# 2022_EDA_2.net
KiCad netlist of a schematic drawn in EasyEDA Pro
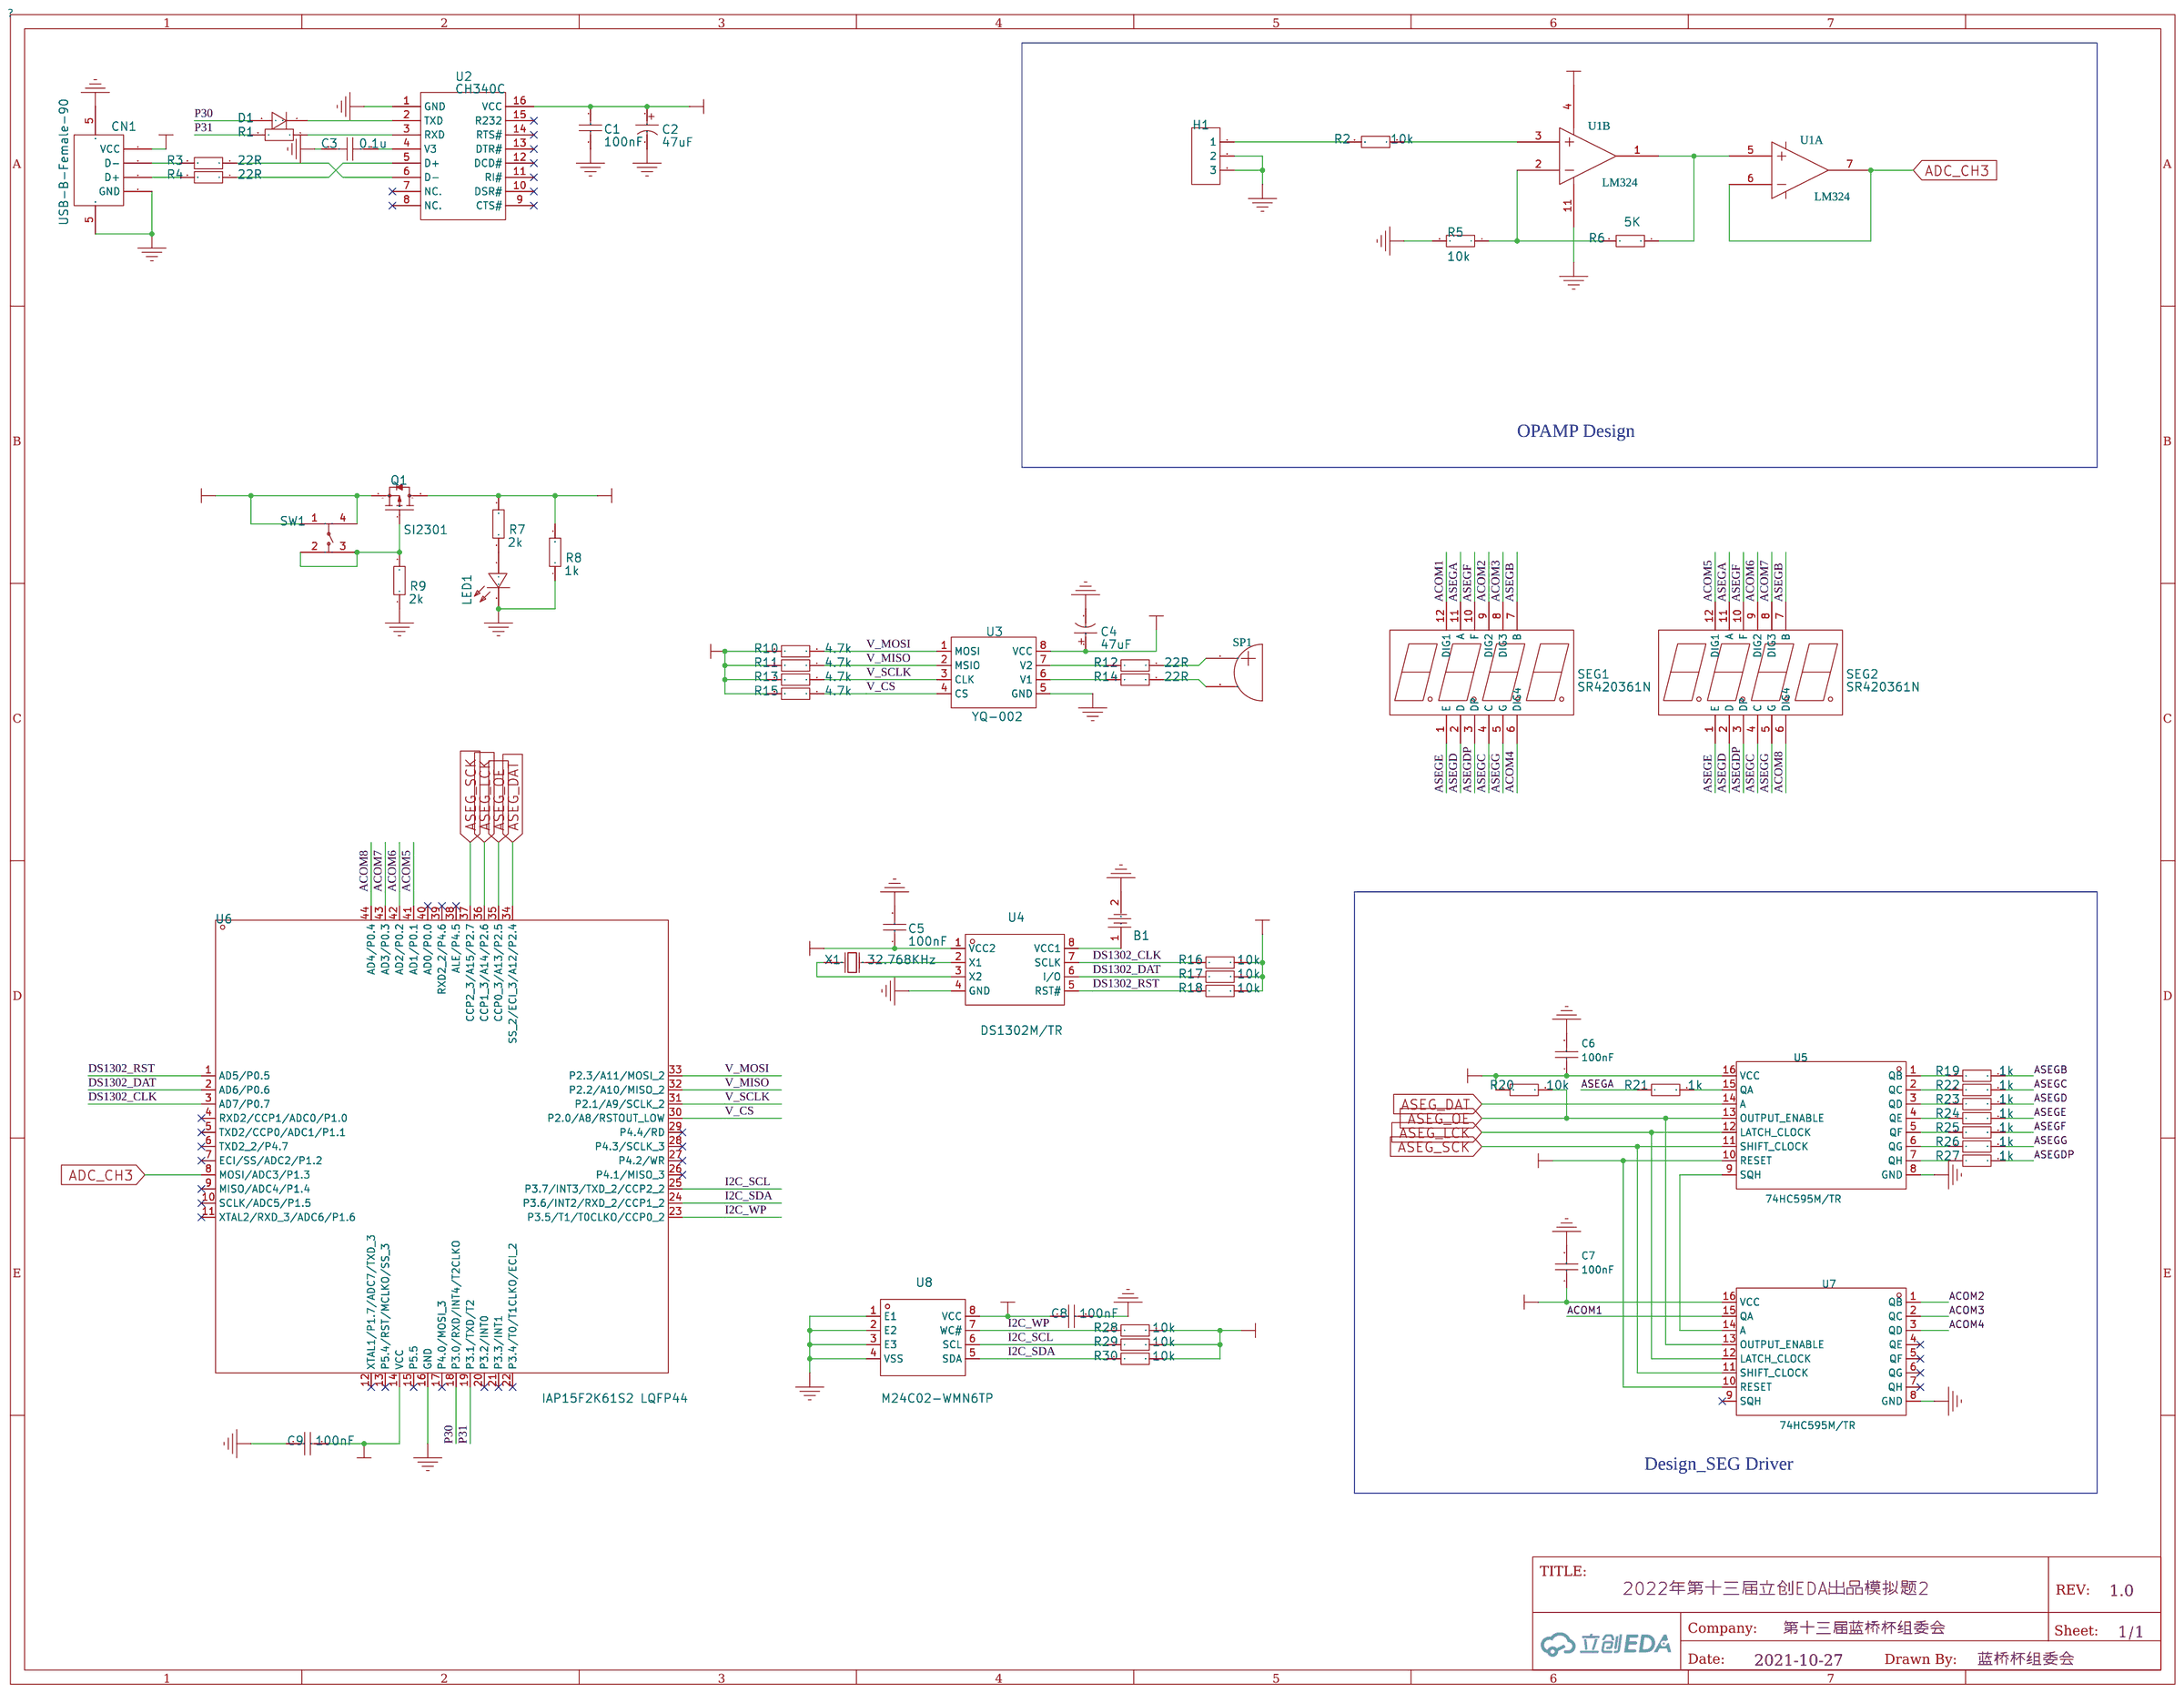
[diagram p0: schematic sheet]

(export (version "E")
  (design (tool "Eeschema 10.0.6"))
  (components
    (comp (ref "B1")
      (value "CR1220-2")
      (fields (field (name "Manufacturer") "Q&amp;J"))
      (libsource (lib "easyedapro") (part "CR1220-2"))
    )
    (comp (ref "C1")
      (value "100nF")
      (fields (field (name "Manufacturer Part") "0805F104M500NT") (field (name "Manufacturer") "FH"))
      (libsource (lib "easyedapro") (part "100nF"))
    )
    (comp (ref "C2")
      (value "47uF")
      (fields (field (name "Manufacturer Part") "VES470M1HTR-0607") (field (name "Manufacturer") "LELON"))
      (libsource (lib "easyedapro") (part "47uF"))
    )
    (comp (ref "C3") (value "0.1u") (libsource (lib "easyedapro") (part "0.1u")))
    (comp (ref "C4")
      (value "47uF")
      (fields (field (name "Manufacturer Part") "VES470M1HTR-0607") (field (name "Manufacturer") "LELON"))
      (libsource (lib "easyedapro") (part "47uF"))
    )
    (comp (ref "C5")
      (value "100nF")
      (fields (field (name "Manufacturer Part") "0805F104M500NT") (field (name "Manufacturer") "FH"))
      (libsource (lib "easyedapro") (part "100nF"))
    )
    (comp (ref "C6") (value "100nF") (libsource (lib "") (part "100nF_1")))
    (comp (ref "C7") (value "100nF") (libsource (lib "") (part "100nF_1")))
    (comp (ref "C8")
      (value "100nF")
      (fields (field (name "Manufacturer Part") "0805F104M500NT") (field (name "Manufacturer") "FH"))
      (libsource (lib "easyedapro") (part "100nF"))
    )
    (comp (ref "C9")
      (value "100nF")
      (fields (field (name "Manufacturer Part") "0805F104M500NT") (field (name "Manufacturer") "FH"))
      (libsource (lib "easyedapro") (part "100nF"))
    )
    (comp (ref "CN1")
      (value "USB-B-Female-90")
      (fields (field (name "Manufacturer Part") "USB-BF90") (field (name "Manufacturer") "ValuePro"))
      (libsource (lib "easyedapro") (part "USB-B-Female-90"))
    )
    (comp (ref "D1")
      (value "KLL4148")
      (fields (field (name "Manufacturer") "KEXIN"))
      (libsource (lib "easyedapro") (part "KLL4148"))
    )
    (comp (ref "H1") (value "HDR-F-2.54_1x3") (libsource (lib "easyedapro") (part "HDR-F-2.54_1x3")))
    (comp (ref "LED1")
      (value "17-21URC/TR8")
      (fields (field (name "Manufacturer") "Everlight Elec"))
      (libsource (lib "easyedapro") (part "17-21URC/TR8"))
    )
    (comp (ref "Q1")
      (value "SI2301")
      (fields (field (name "Manufacturer") "Hottech"))
      (libsource (lib "easyedapro") (part "SI2301"))
    )
    (comp (ref "R1")
      (value "1k")
      (fields (field (name "Manufacturer Part") "080500J0104T5E") (field (name "Manufacturer") "UniOhm"))
      (libsource (lib "easyedapro") (part "22R"))
    )
    (comp (ref "R2")
      (value "10k")
      (fields (field (name "Manufacturer Part") "080500J0104T5E") (field (name "Manufacturer") "UniOhm"))
      (libsource (lib "easyedapro") (part "22R"))
    )
    (comp (ref "R3")
      (value "22R")
      (fields (field (name "Manufacturer Part") "080500J0104T5E") (field (name "Manufacturer") "UniOhm"))
      (libsource (lib "easyedapro") (part "22R"))
    )
    (comp (ref "R4")
      (value "22R")
      (fields (field (name "Manufacturer Part") "080500J0104T5E") (field (name "Manufacturer") "UniOhm"))
      (libsource (lib "easyedapro") (part "22R"))
    )
    (comp (ref "R5")
      (value "10k")
      (fields (field (name "Manufacturer Part") "080500J0104T5E") (field (name "Manufacturer") "UniOhm"))
      (libsource (lib "easyedapro") (part "22R"))
    )
    (comp (ref "R6")
      (value "5K")
      (fields (field (name "Manufacturer Part") "080500J0104T5E") (field (name "Manufacturer") "UniOhm"))
      (libsource (lib "easyedapro") (part "22R"))
    )
    (comp (ref "R7")
      (value "2k")
      (fields (field (name "Manufacturer Part") "080500J0104T5E") (field (name "Manufacturer") "UniOhm"))
      (libsource (lib "easyedapro") (part "22R"))
    )
    (comp (ref "R8")
      (value "1k")
      (fields (field (name "Manufacturer Part") "080500J0104T5E") (field (name "Manufacturer") "UniOhm"))
      (libsource (lib "easyedapro") (part "22R"))
    )
    (comp (ref "R9")
      (value "2k")
      (fields (field (name "Manufacturer Part") "080500J0104T5E") (field (name "Manufacturer") "UniOhm"))
      (libsource (lib "easyedapro") (part "22R"))
    )
    (comp (ref "R10")
      (value "4.7k")
      (fields (field (name "Manufacturer Part") "080500J0104T5E") (field (name "Manufacturer") "UniOhm"))
      (libsource (lib "easyedapro") (part "22R"))
    )
    (comp (ref "R11")
      (value "4.7k")
      (fields (field (name "Manufacturer Part") "080500J0104T5E") (field (name "Manufacturer") "UniOhm"))
      (libsource (lib "easyedapro") (part "22R"))
    )
    (comp (ref "R12")
      (value "22R")
      (fields (field (name "Manufacturer Part") "080500J0104T5E") (field (name "Manufacturer") "UniOhm"))
      (libsource (lib "easyedapro") (part "22R"))
    )
    (comp (ref "R13")
      (value "4.7k")
      (fields (field (name "Manufacturer Part") "080500J0104T5E") (field (name "Manufacturer") "UniOhm"))
      (libsource (lib "easyedapro") (part "22R"))
    )
    (comp (ref "R14")
      (value "22R")
      (fields (field (name "Manufacturer Part") "080500J0104T5E") (field (name "Manufacturer") "UniOhm"))
      (libsource (lib "easyedapro") (part "22R"))
    )
    (comp (ref "R15")
      (value "4.7k")
      (fields (field (name "Manufacturer Part") "080500J0104T5E") (field (name "Manufacturer") "UniOhm"))
      (libsource (lib "easyedapro") (part "22R"))
    )
    (comp (ref "R16")
      (value "10k")
      (fields (field (name "Manufacturer Part") "080500J0104T5E") (field (name "Manufacturer") "UniOhm"))
      (libsource (lib "easyedapro") (part "22R"))
    )
    (comp (ref "R17")
      (value "10k")
      (fields (field (name "Manufacturer Part") "080500J0104T5E") (field (name "Manufacturer") "UniOhm"))
      (libsource (lib "easyedapro") (part "22R"))
    )
    (comp (ref "R18")
      (value "10k")
      (fields (field (name "Manufacturer Part") "080500J0104T5E") (field (name "Manufacturer") "UniOhm"))
      (libsource (lib "easyedapro") (part "22R"))
    )
    (comp (ref "R19")
      (value "1k")
      (fields (field (name "Manufacturer Part") "080500J0104T5E") (field (name "Manufacturer") "UniOhm"))
      (libsource (lib "easyedapro") (part "22R"))
    )
    (comp (ref "R20")
      (value "10k")
      (fields (field (name "Manufacturer Part") "080500J0104T5E") (field (name "Manufacturer") "UniOhm"))
      (libsource (lib "easyedapro") (part "22R"))
    )
    (comp (ref "R21")
      (value "1k")
      (fields (field (name "Manufacturer Part") "080500J0104T5E") (field (name "Manufacturer") "UniOhm"))
      (libsource (lib "easyedapro") (part "22R"))
    )
    (comp (ref "R22")
      (value "1k")
      (fields (field (name "Manufacturer Part") "080500J0104T5E") (field (name "Manufacturer") "UniOhm"))
      (libsource (lib "easyedapro") (part "22R"))
    )
    (comp (ref "R23")
      (value "1k")
      (fields (field (name "Manufacturer Part") "080500J0104T5E") (field (name "Manufacturer") "UniOhm"))
      (libsource (lib "easyedapro") (part "22R"))
    )
    (comp (ref "R24")
      (value "1k")
      (fields (field (name "Manufacturer Part") "080500J0104T5E") (field (name "Manufacturer") "UniOhm"))
      (libsource (lib "easyedapro") (part "22R"))
    )
    (comp (ref "R25")
      (value "1k")
      (fields (field (name "Manufacturer Part") "080500J0104T5E") (field (name "Manufacturer") "UniOhm"))
      (libsource (lib "easyedapro") (part "22R"))
    )
    (comp (ref "R26")
      (value "1k")
      (fields (field (name "Manufacturer Part") "080500J0104T5E") (field (name "Manufacturer") "UniOhm"))
      (libsource (lib "easyedapro") (part "22R"))
    )
    (comp (ref "R27")
      (value "1k")
      (fields (field (name "Manufacturer Part") "080500J0104T5E") (field (name "Manufacturer") "UniOhm"))
      (libsource (lib "easyedapro") (part "22R"))
    )
    (comp (ref "R28")
      (value "10k")
      (fields (field (name "Manufacturer Part") "080500J0104T5E") (field (name "Manufacturer") "UniOhm"))
      (libsource (lib "easyedapro") (part "22R"))
    )
    (comp (ref "R29")
      (value "10k")
      (fields (field (name "Manufacturer Part") "080500J0104T5E") (field (name "Manufacturer") "UniOhm"))
      (libsource (lib "easyedapro") (part "22R"))
    )
    (comp (ref "R30")
      (value "10k")
      (fields (field (name "Manufacturer Part") "080500J0104T5E") (field (name "Manufacturer") "UniOhm"))
      (libsource (lib "easyedapro") (part "22R"))
    )
    (comp (ref "SEG1")
      (value "SR420361N")
      (fields (field (name "Manufacturer") "Wuxi ARK Tech Elec"))
      (libsource (lib "easyedapro") (part "SR420361N"))
    )
    (comp (ref "SEG2")
      (value "SR420361N")
      (fields (field (name "Manufacturer") "Wuxi ARK Tech Elec"))
      (libsource (lib "easyedapro") (part "SR420361N"))
    )
    (comp (ref "SP1") (value "BUZZER") (libsource (lib "easyedapro") (part "BUZZER")))
    (comp (ref "SW1")
      (value "TS-1159UB-B-D-BL")
      (fields (field (name "Manufacturer") "XKB Connectivity"))
      (libsource (lib "easyedapro") (part "TS-1159UB-B-D-BL"))
    )
    (comp (ref "U1") (value "LM324") (libsource (lib "easyedapro") (part "LM324")))
    (comp (ref "U2")
      (value "CH340C")
      (fields (field (name "Manufacturer") "WCH"))
      (libsource (lib "easyedapro") (part "CH340C"))
    )
    (comp (ref "U3") (value "YQ-002") (libsource (lib "easyedapro") (part "YQ-002")))
    (comp (ref "U4")
      (value "DS1302M/TR")
      (fields (field (name "Manufacturer") "HGSEMI"))
      (libsource (lib "easyedapro") (part "DS1302M/TR"))
    )
    (comp (ref "U5") (value "74HC595M/TR") (libsource (lib "easyedapro") (part "74HC595M/TR")))
    (comp (ref "U6")
      (value "IAP15F2K61S2 LQFP44")
      (fields (field (name "Manufacturer") "STC"))
      (libsource (lib "easyedapro") (part "IAP15F2K61S2 LQFP44"))
    )
    (comp (ref "U7") (value "74HC595M/TR") (libsource (lib "easyedapro") (part "74HC595M/TR")))
    (comp (ref "U8")
      (value "M24C02-WMN6TP")
      (fields (field (name "Manufacturer") "STMicroelectronics"))
      (libsource (lib "easyedapro") (part "M24C02-WMN6TP"))
    )
    (comp (ref "X1")
      (value "32.768KHz")
      (fields
        (field (name "Manufacturer Part") "6K832768F12UB")
        (field (name "Manufacturer") "SHENZHEN CRYSTAL TECH")
      )
      (libsource (lib "easyedapro") (part "32.768KHz"))
    )
  )
  (nets
    (net (code "1") (name "/ACOM1") (class "Default")
      (node (ref "SEG1") (pin "12") (pinfunction "DIG1_12") (pintype "input"))
      (node (ref "U7") (pin "15") (pinfunction "QA_15") (pintype "input"))
    )
    (net (code "2") (name "/ACOM2") (class "Default")
      (node (ref "SEG1") (pin "9") (pinfunction "DIG2_9") (pintype "input"))
      (node (ref "U7") (pin "1") (pinfunction "QB_1") (pintype "input"))
    )
    (net (code "3") (name "/ACOM3") (class "Default")
      (node (ref "SEG1") (pin "8") (pinfunction "DIG3_8") (pintype "input"))
      (node (ref "U7") (pin "2") (pinfunction "QC_2") (pintype "input"))
    )
    (net (code "4") (name "/ACOM4") (class "Default")
      (node (ref "SEG1") (pin "6") (pinfunction "DIG4_6") (pintype "input"))
      (node (ref "U7") (pin "3") (pinfunction "QD_3") (pintype "input"))
    )
    (net (code "5") (name "/ACOM5") (class "Default")
      (node (ref "SEG2") (pin "12") (pinfunction "DIG1_12") (pintype "input"))
      (node (ref "U6") (pin "41") (pinfunction "AD1/P0.1_41") (pintype "input"))
    )
    (net (code "6") (name "/ACOM6") (class "Default")
      (node (ref "SEG2") (pin "9") (pinfunction "DIG2_9") (pintype "input"))
      (node (ref "U6") (pin "42") (pinfunction "AD2/P0.2_42") (pintype "input"))
    )
    (net (code "7") (name "/ACOM7") (class "Default")
      (node (ref "SEG2") (pin "8") (pinfunction "DIG3_8") (pintype "input"))
      (node (ref "U6") (pin "43") (pinfunction "AD3/P0.3_43") (pintype "input"))
    )
    (net (code "8") (name "/ACOM8") (class "Default")
      (node (ref "SEG2") (pin "6") (pinfunction "DIG4_6") (pintype "input"))
      (node (ref "U6") (pin "44") (pinfunction "AD4/P0.4_44") (pintype "input"))
    )
    (net (code "9") (name "/ASEGA") (class "Default")
      (node (ref "R21") (pin "1") (pinfunction "1_1") (pintype "input"))
      (node (ref "SEG1") (pin "11") (pinfunction "A_11") (pintype "input"))
      (node (ref "SEG2") (pin "11") (pinfunction "A_11") (pintype "input"))
    )
    (net (code "10") (name "/ASEGB") (class "Default")
      (node (ref "R19") (pin "2") (pinfunction "2_2") (pintype "input"))
      (node (ref "SEG1") (pin "7") (pinfunction "B_7") (pintype "input"))
      (node (ref "SEG2") (pin "7") (pinfunction "B_7") (pintype "input"))
    )
    (net (code "11") (name "/ASEGC") (class "Default")
      (node (ref "R22") (pin "2") (pinfunction "2_2") (pintype "input"))
      (node (ref "SEG1") (pin "4") (pinfunction "C_4") (pintype "input"))
      (node (ref "SEG2") (pin "4") (pinfunction "C_4") (pintype "input"))
    )
    (net (code "12") (name "/ASEGD") (class "Default")
      (node (ref "R23") (pin "2") (pinfunction "2_2") (pintype "input"))
      (node (ref "SEG1") (pin "2") (pinfunction "D_2") (pintype "input"))
      (node (ref "SEG2") (pin "2") (pinfunction "D_2") (pintype "input"))
    )
    (net (code "13") (name "/ASEGDP") (class "Default")
      (node (ref "R27") (pin "2") (pinfunction "2_2") (pintype "input"))
      (node (ref "SEG1") (pin "3") (pinfunction "DP_3") (pintype "input"))
      (node (ref "SEG2") (pin "3") (pinfunction "DP_3") (pintype "input"))
    )
    (net (code "14") (name "/ASEGE") (class "Default")
      (node (ref "R24") (pin "2") (pinfunction "2_2") (pintype "input"))
      (node (ref "SEG1") (pin "1") (pinfunction "E_1") (pintype "input"))
      (node (ref "SEG2") (pin "1") (pinfunction "E_1") (pintype "input"))
    )
    (net (code "15") (name "/ASEGF") (class "Default")
      (node (ref "R25") (pin "2") (pinfunction "2_2") (pintype "input"))
      (node (ref "SEG1") (pin "10") (pinfunction "F_10") (pintype "input"))
      (node (ref "SEG2") (pin "10") (pinfunction "F_10") (pintype "input"))
    )
    (net (code "16") (name "/ASEGG") (class "Default")
      (node (ref "R26") (pin "2") (pinfunction "2_2") (pintype "input"))
      (node (ref "SEG1") (pin "5") (pinfunction "G_5") (pintype "input"))
      (node (ref "SEG2") (pin "5") (pinfunction "G_5") (pintype "input"))
    )
    (net (code "17") (name "/DS1302_CLK") (class "Default")
      (node (ref "R16") (pin "1") (pinfunction "1_1") (pintype "input"))
      (node (ref "U4") (pin "7") (pinfunction "SCLK_7") (pintype "input"))
      (node (ref "U6") (pin "3") (pinfunction "AD7/P0.7_3") (pintype "input"))
    )
    (net (code "18") (name "/DS1302_DAT") (class "Default")
      (node (ref "R17") (pin "1") (pinfunction "1_1") (pintype "input"))
      (node (ref "U4") (pin "6") (pinfunction "I/O_6") (pintype "input"))
      (node (ref "U6") (pin "2") (pinfunction "AD6/P0.6_2") (pintype "input"))
    )
    (net (code "19") (name "/DS1302_RST") (class "Default")
      (node (ref "R18") (pin "1") (pinfunction "1_1") (pintype "input"))
      (node (ref "U4") (pin "5") (pinfunction "RST#_5") (pintype "input"))
      (node (ref "U6") (pin "1") (pinfunction "AD5/P0.5_1") (pintype "input"))
    )
    (net (code "20") (name "/I2C_SCL") (class "Default")
      (node (ref "R29") (pin "1") (pinfunction "1_1") (pintype "input"))
      (node (ref "U6") (pin "25") (pinfunction "P3.7/INT3/TXD_2/CCP2_2_25") (pintype "input"))
      (node (ref "U8") (pin "6") (pinfunction "SCL_6") (pintype "input"))
    )
    (net (code "21") (name "/I2C_SDA") (class "Default")
      (node (ref "R30") (pin "1") (pinfunction "1_1") (pintype "input"))
      (node (ref "U6") (pin "24") (pinfunction "P3.6/INT2/RXD_2/CCP1_2_24") (pintype "input"))
      (node (ref "U8") (pin "5") (pinfunction "SDA_5") (pintype "input"))
    )
    (net (code "22") (name "/I2C_WP") (class "Default")
      (node (ref "R28") (pin "1") (pinfunction "1_1") (pintype "input"))
      (node (ref "U6") (pin "23") (pinfunction "P3.5/T1/T0CLKO/CCP0_2_23") (pintype "input"))
      (node (ref "U8") (pin "7") (pinfunction "WC#_7") (pintype "input"))
    )
    (net (code "23") (name "/P30") (class "Default")
      (node (ref "D1") (pin "2") (pinfunction "A_2") (pintype "input"))
      (node (ref "U6") (pin "18") (pinfunction "P3.0/RXD/INT4/T2CLKO_18") (pintype "input"))
    )
    (net (code "24") (name "/P31") (class "Default")
      (node (ref "R1") (pin "2") (pinfunction "2_2") (pintype "input"))
      (node (ref "U6") (pin "19") (pinfunction "P3.1/TXD/T2_19") (pintype "input"))
    )
    (net (code "25") (name "/V_CS") (class "Default")
      (node (ref "R15") (pin "1") (pinfunction "1_1") (pintype "input"))
      (node (ref "U3") (pin "4") (pinfunction "CS_4") (pintype "input"))
      (node (ref "U6") (pin "30") (pinfunction "P2.0/A8/RSTOUT_LOW_30") (pintype "input"))
    )
    (net (code "26") (name "/V_MISO") (class "Default")
      (node (ref "R11") (pin "1") (pinfunction "1_1") (pintype "input"))
      (node (ref "U3") (pin "2") (pinfunction "MSIO_2") (pintype "input"))
      (node (ref "U6") (pin "32") (pinfunction "P2.2/A10/MISO_2_32") (pintype "input"))
    )
    (net (code "27") (name "/V_MOSI") (class "Default")
      (node (ref "R10") (pin "1") (pinfunction "1_1") (pintype "input"))
      (node (ref "U3") (pin "1") (pinfunction "MOSI_1") (pintype "input"))
      (node (ref "U6") (pin "33") (pinfunction "P2.3/A11/MOSI_2_33") (pintype "input"))
    )
    (net (code "28") (name "/V_SCLK") (class "Default")
      (node (ref "R13") (pin "1") (pinfunction "1_1") (pintype "input"))
      (node (ref "U3") (pin "3") (pinfunction "CLK_3") (pintype "input"))
      (node (ref "U6") (pin "31") (pinfunction "P2.1/A9/SCLK_2_31") (pintype "input"))
    )
    (net (code "29") (name "ADC_CH3") (class "Default")
      (node (ref "U1") (pin "6") (pintype "input"))
      (node (ref "U1") (pin "7") (pintype "input"))
      (node (ref "U6") (pin "8") (pinfunction "MOSI/ADC3/P1.3_8") (pintype "input"))
    )
    (net (code "30") (name "ASEG_DAT") (class "Default")
      (node (ref "U5") (pin "14") (pinfunction "A_14") (pintype "input"))
      (node (ref "U6") (pin "34") (pinfunction "SS_2/ECI_3/A12/P2.4_34") (pintype "input"))
    )
    (net (code "31") (name "ASEG_LCK") (class "Default")
      (node (ref "U5") (pin "12") (pinfunction "LATCH_CLOCK_12") (pintype "input"))
      (node (ref "U6") (pin "36") (pinfunction "CCP1_3/A14/P2.6_36") (pintype "input"))
      (node (ref "U7") (pin "12") (pinfunction "LATCH_CLOCK_12") (pintype "input"))
    )
    (net (code "32") (name "ASEG_OE") (class "Default")
      (node (ref "R20") (pin "2") (pinfunction "2_2") (pintype "input"))
      (node (ref "U5") (pin "13") (pinfunction "OUTPUT_ENABLE_13") (pintype "input"))
      (node (ref "U6") (pin "35") (pinfunction "CCP0_3/A13/P2.5_35") (pintype "input"))
      (node (ref "U7") (pin "13") (pinfunction "OUTPUT_ENABLE_13") (pintype "input"))
    )
    (net (code "33") (name "ASEG_SCK") (class "Default")
      (node (ref "U5") (pin "11") (pinfunction "SHIFT_CLOCK_11") (pintype "input"))
      (node (ref "U6") (pin "37") (pinfunction "CCP2_3/A15/P2.7_37") (pintype "input"))
      (node (ref "U7") (pin "11") (pinfunction "SHIFT_CLOCK_11") (pintype "input"))
    )
    (net (code "34") (name "GND") (class "Default")
      (node (ref "B1") (pin "2") (pinfunction "2_2") (pintype "input"))
      (node (ref "C1") (pin "1") (pinfunction "1_1") (pintype "input"))
      (node (ref "C2") (pin "2") (pinfunction "2_2") (pintype "input"))
      (node (ref "C3") (pin "1") (pinfunction "1_1") (pintype "input"))
      (node (ref "C4") (pin "2") (pinfunction "2_2") (pintype "input"))
      (node (ref "C5") (pin "2") (pinfunction "2_2") (pintype "input"))
      (node (ref "C6") (pin "2") (pinfunction "2_2") (pintype "input"))
      (node (ref "C7") (pin "2") (pinfunction "2_2") (pintype "input"))
      (node (ref "C8") (pin "2") (pinfunction "2_2") (pintype "input"))
      (node (ref "C9") (pin "1") (pinfunction "1_1") (pintype "input"))
      (node (ref "CN1") (pin "4") (pinfunction "GND_4") (pintype "input"))
      (node (ref "CN1") (pin "5") (pinfunction "SH2_5") (pintype "input"))
      (node (ref "H1") (pin "2") (pinfunction "2_2") (pintype "input"))
      (node (ref "H1") (pin "3") (pinfunction "3_3") (pintype "input"))
      (node (ref "LED1") (pin "2") (pinfunction "K_2") (pintype "input"))
      (node (ref "R5") (pin "2") (pinfunction "2_2") (pintype "input"))
      (node (ref "R8") (pin "1") (pinfunction "1_1") (pintype "input"))
      (node (ref "R9") (pin "1") (pinfunction "1_1") (pintype "input"))
      (node (ref "U1") (pin "11") (pintype "input"))
      (node (ref "U2") (pin "1") (pinfunction "GND_1") (pintype "input"))
      (node (ref "U3") (pin "5") (pinfunction "GND_5") (pintype "input"))
      (node (ref "U4") (pin "4") (pinfunction "GND_4") (pintype "input"))
      (node (ref "U5") (pin "8") (pinfunction "GND_8") (pintype "input"))
      (node (ref "U6") (pin "16") (pinfunction "GND_16") (pintype "input"))
      (node (ref "U7") (pin "8") (pinfunction "GND_8") (pintype "input"))
      (node (ref "U8") (pin "1") (pinfunction "E1_1") (pintype "input"))
      (node (ref "U8") (pin "2") (pinfunction "E2_2") (pintype "input"))
      (node (ref "U8") (pin "3") (pinfunction "E3_3") (pintype "input"))
      (node (ref "U8") (pin "4") (pinfunction "VSS_4") (pintype "input"))
    )
    (net (code "35") (name "Net-(CN1-D+)") (class "Default")
      (node (ref "CN1") (pin "3") (pinfunction "D+_3") (pintype "input"))
      (node (ref "R4") (pin "2") (pinfunction "2_2") (pintype "input"))
    )
    (net (code "36") (name "Net-(CN1-D-)") (class "Default")
      (node (ref "CN1") (pin "2") (pinfunction "D-_2") (pintype "input"))
      (node (ref "R3") (pin "2") (pinfunction "2_2") (pintype "input"))
    )
    (net (code "37") (name "Net-(D1-C)") (class "Default")
      (node (ref "D1") (pin "1") (pinfunction "C_1") (pintype "input"))
      (node (ref "U2") (pin "2") (pinfunction "TXD_2") (pintype "input"))
    )
    (net (code "38") (name "Net-(H1-Pad1)") (class "Default")
      (node (ref "H1") (pin "1") (pinfunction "1_1") (pintype "input"))
      (node (ref "R2") (pin "2") (pinfunction "2_2") (pintype "input"))
    )
    (net (code "39") (name "Net-(LED1-A)") (class "Default")
      (node (ref "LED1") (pin "1") (pinfunction "A_1") (pintype "input"))
      (node (ref "R7") (pin "1") (pinfunction "1_1") (pintype "input"))
    )
    (net (code "40") (name "Net-(Q1-G)") (class "Default")
      (node (ref "Q1") (pin "1") (pinfunction "G_1") (pintype "input"))
      (node (ref "R9") (pin "2") (pinfunction "2_2") (pintype "input"))
      (node (ref "SW1") (pin "2") (pinfunction "4_2") (pintype "input"))
      (node (ref "SW1") (pin "3") (pinfunction "3_3") (pintype "input"))
    )
    (net (code "41") (name "Net-(R2-Pad1)") (class "Default")
      (node (ref "R2") (pin "1") (pinfunction "1_1") (pintype "input"))
      (node (ref "U1") (pin "3") (pintype "input"))
    )
    (net (code "42") (name "Net-(R5-Pad1)") (class "Default")
      (node (ref "R5") (pin "1") (pinfunction "1_1") (pintype "input"))
      (node (ref "R6") (pin "2") (pinfunction "2_2") (pintype "input"))
      (node (ref "U1") (pin "2") (pintype "input"))
    )
    (net (code "43") (name "Net-(R6-Pad1)") (class "Default")
      (node (ref "R6") (pin "1") (pinfunction "1_1") (pintype "input"))
      (node (ref "U1") (pin "1") (pintype "input"))
      (node (ref "U1") (pin "5") (pintype "input"))
    )
    (net (code "44") (name "Net-(R12-Pad2)") (class "Default")
      (node (ref "R12") (pin "2") (pinfunction "2_2") (pintype "input"))
      (node (ref "SP1") (pin "1") (pinfunction "1_1") (pintype "input"))
    )
    (net (code "45") (name "Net-(R14-Pad2)") (class "Default")
      (node (ref "R14") (pin "2") (pinfunction "2_2") (pintype "input"))
      (node (ref "SP1") (pin "2") (pinfunction "2_2") (pintype "input"))
    )
    (net (code "46") (name "Net-(U2-D+)") (class "Default")
      (node (ref "R4") (pin "1") (pinfunction "1_1") (pintype "input"))
      (node (ref "U2") (pin "5") (pinfunction "D+_5") (pintype "input"))
    )
    (net (code "47") (name "Net-(U2-D-)") (class "Default")
      (node (ref "R3") (pin "1") (pinfunction "1_1") (pintype "input"))
      (node (ref "U2") (pin "6") (pinfunction "D-_6") (pintype "input"))
    )
    (net (code "48") (name "Net-(U2-RXD)") (class "Default")
      (node (ref "R1") (pin "1") (pinfunction "1_1") (pintype "input"))
      (node (ref "U2") (pin "3") (pinfunction "RXD_3") (pintype "input"))
    )
    (net (code "49") (name "Net-(U2-V3)") (class "Default")
      (node (ref "C3") (pin "2") (pinfunction "2_2") (pintype "input"))
      (node (ref "U2") (pin "4") (pinfunction "V3_4") (pintype "input"))
    )
    (net (code "50") (name "Net-(U3-V1)") (class "Default")
      (node (ref "R14") (pin "1") (pinfunction "1_1") (pintype "input"))
      (node (ref "U3") (pin "6") (pinfunction "V1_6") (pintype "input"))
    )
    (net (code "51") (name "Net-(U3-V2)") (class "Default")
      (node (ref "R12") (pin "1") (pinfunction "1_1") (pintype "input"))
      (node (ref "U3") (pin "7") (pinfunction "V2_7") (pintype "input"))
    )
    (net (code "52") (name "Net-(U4-VCC1)") (class "Default")
      (node (ref "B1") (pin "1") (pinfunction "1_1") (pintype "input"))
      (node (ref "U4") (pin "8") (pinfunction "VCC1_8") (pintype "input"))
    )
    (net (code "53") (name "Net-(U4-X1)") (class "Default")
      (node (ref "U4") (pin "2") (pinfunction "X1_2") (pintype "input"))
      (node (ref "X1") (pin "2") (pinfunction "OSC2_2") (pintype "input"))
    )
    (net (code "54") (name "Net-(U4-X2)") (class "Default")
      (node (ref "U4") (pin "3") (pinfunction "X2_3") (pintype "input"))
      (node (ref "X1") (pin "1") (pinfunction "OSC1_1") (pintype "input"))
    )
    (net (code "55") (name "Net-(U5-QA)") (class "Default")
      (node (ref "R21") (pin "2") (pinfunction "2_2") (pintype "input"))
      (node (ref "U5") (pin "15") (pinfunction "QA_15") (pintype "input"))
    )
    (net (code "56") (name "Net-(U5-QB)") (class "Default")
      (node (ref "R19") (pin "1") (pinfunction "1_1") (pintype "input"))
      (node (ref "U5") (pin "1") (pinfunction "QB_1") (pintype "input"))
    )
    (net (code "57") (name "Net-(U5-QC)") (class "Default")
      (node (ref "R22") (pin "1") (pinfunction "1_1") (pintype "input"))
      (node (ref "U5") (pin "2") (pinfunction "QC_2") (pintype "input"))
    )
    (net (code "58") (name "Net-(U5-QD)") (class "Default")
      (node (ref "R23") (pin "1") (pinfunction "1_1") (pintype "input"))
      (node (ref "U5") (pin "3") (pinfunction "QD_3") (pintype "input"))
    )
    (net (code "59") (name "Net-(U5-QE)") (class "Default")
      (node (ref "R24") (pin "1") (pinfunction "1_1") (pintype "input"))
      (node (ref "U5") (pin "4") (pinfunction "QE_4") (pintype "input"))
    )
    (net (code "60") (name "Net-(U5-QF)") (class "Default")
      (node (ref "R25") (pin "1") (pinfunction "1_1") (pintype "input"))
      (node (ref "U5") (pin "5") (pinfunction "QF_5") (pintype "input"))
    )
    (net (code "61") (name "Net-(U5-QG)") (class "Default")
      (node (ref "R26") (pin "1") (pinfunction "1_1") (pintype "input"))
      (node (ref "U5") (pin "6") (pinfunction "QG_6") (pintype "input"))
    )
    (net (code "62") (name "Net-(U5-QH)") (class "Default")
      (node (ref "R27") (pin "1") (pinfunction "1_1") (pintype "input"))
      (node (ref "U5") (pin "7") (pinfunction "QH_7") (pintype "input"))
    )
    (net (code "63") (name "Net-(U5-SQH)") (class "Default")
      (node (ref "U5") (pin "9") (pinfunction "SQH_9") (pintype "input"))
      (node (ref "U7") (pin "14") (pinfunction "A_14") (pintype "input"))
    )
    (net (code "64") (name "VDD_NODE_A") (class "Default")
      (node (ref "C4") (pin "1") (pinfunction "1_1") (pintype "input"))
      (node (ref "C5") (pin "1") (pinfunction "1_1") (pintype "input"))
      (node (ref "C6") (pin "1") (pinfunction "1_1") (pintype "input"))
      (node (ref "C7") (pin "1") (pinfunction "1_1") (pintype "input"))
      (node (ref "C8") (pin "1") (pinfunction "1_1") (pintype "input"))
      (node (ref "C9") (pin "2") (pinfunction "2_2") (pintype "input"))
      (node (ref "Q1") (pin "3") (pinfunction "D_3") (pintype "input"))
      (node (ref "R10") (pin "2") (pinfunction "2_2") (pintype "input"))
      (node (ref "R11") (pin "2") (pinfunction "2_2") (pintype "input"))
      (node (ref "R13") (pin "2") (pinfunction "2_2") (pintype "input"))
      (node (ref "R15") (pin "2") (pinfunction "2_2") (pintype "input"))
      (node (ref "R16") (pin "2") (pinfunction "2_2") (pintype "input"))
      (node (ref "R17") (pin "2") (pinfunction "2_2") (pintype "input"))
      (node (ref "R18") (pin "2") (pinfunction "2_2") (pintype "input"))
      (node (ref "R20") (pin "1") (pinfunction "1_1") (pintype "input"))
      (node (ref "R28") (pin "2") (pinfunction "2_2") (pintype "input"))
      (node (ref "R29") (pin "2") (pinfunction "2_2") (pintype "input"))
      (node (ref "R30") (pin "2") (pinfunction "2_2") (pintype "input"))
      (node (ref "R7") (pin "2") (pinfunction "2_2") (pintype "input"))
      (node (ref "R8") (pin "2") (pinfunction "2_2") (pintype "input"))
      (node (ref "U1") (pin "4") (pintype "input"))
      (node (ref "U3") (pin "8") (pinfunction "VCC_8") (pintype "input"))
      (node (ref "U4") (pin "1") (pinfunction "VCC2_1") (pintype "input"))
      (node (ref "U5") (pin "10") (pinfunction "RESET_10") (pintype "input"))
      (node (ref "U5") (pin "16") (pinfunction "VCC_16") (pintype "input"))
      (node (ref "U6") (pin "14") (pinfunction "VCC_14") (pintype "input"))
      (node (ref "U7") (pin "10") (pinfunction "RESET_10") (pintype "input"))
      (node (ref "U7") (pin "16") (pinfunction "VCC_16") (pintype "input"))
      (node (ref "U8") (pin "8") (pinfunction "VCC_8") (pintype "input"))
    )
    (net (code "65") (name "VUSB") (class "Default")
      (node (ref "C1") (pin "2") (pinfunction "2_2") (pintype "input"))
      (node (ref "C2") (pin "1") (pinfunction "1_1") (pintype "input"))
      (node (ref "CN1") (pin "1") (pinfunction "VCC_1") (pintype "input"))
      (node (ref "Q1") (pin "2") (pinfunction "S_2") (pintype "input"))
      (node (ref "SW1") (pin "1") (pinfunction "1_1") (pintype "input"))
      (node (ref "SW1") (pin "4") (pinfunction "2_4") (pintype "input"))
      (node (ref "U2") (pin "16") (pinfunction "VCC_16") (pintype "input"))
    )
    (net (code "66") (name "unconnected-(U2-CTS#-Pad9)") (class "Default")
      (node (ref "U2") (pin "9") (pinfunction "CTS#_9") (pintype "input+no_connect"))
    )
    (net (code "67") (name "unconnected-(U2-DCD#-Pad12)") (class "Default")
      (node (ref "U2") (pin "12") (pinfunction "DCD#_12") (pintype "input+no_connect"))
    )
    (net (code "68") (name "unconnected-(U2-DSR#-Pad10)") (class "Default")
      (node (ref "U2") (pin "10") (pinfunction "DSR#_10") (pintype "input+no_connect"))
    )
    (net (code "69") (name "unconnected-(U2-DTR#-Pad13)") (class "Default")
      (node (ref "U2") (pin "13") (pinfunction "DTR#_13") (pintype "input+no_connect"))
    )
    (net (code "70") (name "unconnected-(U2-NC.-Pad7)") (class "Default")
      (node (ref "U2") (pin "7") (pinfunction "NC._7") (pintype "input+no_connect"))
    )
    (net (code "71") (name "unconnected-(U2-NC.-Pad8)") (class "Default")
      (node (ref "U2") (pin "8") (pinfunction "NC._8") (pintype "input+no_connect"))
    )
    (net (code "72") (name "unconnected-(U2-R232-Pad15)") (class "Default")
      (node (ref "U2") (pin "15") (pinfunction "R232_15") (pintype "input+no_connect"))
    )
    (net (code "73") (name "unconnected-(U2-RI#-Pad11)") (class "Default")
      (node (ref "U2") (pin "11") (pinfunction "RI#_11") (pintype "input+no_connect"))
    )
    (net (code "74") (name "unconnected-(U2-RTS#-Pad14)") (class "Default")
      (node (ref "U2") (pin "14") (pinfunction "RTS#_14") (pintype "input+no_connect"))
    )
    (net (code "75") (name "unconnected-(U6-AD0{slash}P0.0-Pad40)") (class "Default")
      (node (ref "U6") (pin "40") (pinfunction "AD0/P0.0_40") (pintype "input+no_connect"))
    )
    (net (code "76") (name "unconnected-(U6-ALE{slash}P4.5-Pad38)") (class "Default")
      (node (ref "U6") (pin "38") (pinfunction "ALE/P4.5_38") (pintype "input+no_connect"))
    )
    (net (code "77") (name "unconnected-(U6-ECI{slash}SS{slash}ADC2{slash}P1.2-Pad7)") (class "Default")
      (node (ref "U6") (pin "7") (pinfunction "ECI/SS/ADC2/P1.2_7") (pintype "input+no_connect"))
    )
    (net (code "78") (name "unconnected-(U6-MISO{slash}ADC4{slash}P1.4-Pad9)") (class "Default")
      (node (ref "U6") (pin "9") (pinfunction "MISO/ADC4/P1.4_9") (pintype "input+no_connect"))
    )
    (net (code "79") (name "unconnected-(U6-P3.2{slash}INT0-Pad20)") (class "Default")
      (node (ref "U6") (pin "20") (pinfunction "P3.2/INT0_20") (pintype "input+no_connect"))
    )
    (net (code "80") (name "unconnected-(U6-P3.3{slash}INT1-Pad21)") (class "Default")
      (node (ref "U6") (pin "21") (pinfunction "P3.3/INT1_21") (pintype "input+no_connect"))
    )
    (net (code "81") (name "unconnected-(U6-P3.4{slash}T0{slash}T1CLKO{slash}ECI_2-Pad22)") (class "Default")
      (node (ref "U6") (pin "22") (pinfunction "P3.4/T0/T1CLKO/ECI_2_22") (pintype "input+no_connect"))
    )
    (net (code "82") (name "unconnected-(U6-P4.0{slash}MOSI_3-Pad17)") (class "Default")
      (node (ref "U6") (pin "17") (pinfunction "P4.0/MOSI_3_17") (pintype "input+no_connect"))
    )
    (net (code "83") (name "unconnected-(U6-P4.1{slash}MISO_3-Pad26)") (class "Default")
      (node (ref "U6") (pin "26") (pinfunction "P4.1/MISO_3_26") (pintype "input+no_connect"))
    )
    (net (code "84") (name "unconnected-(U6-P4.2{slash}WR-Pad27)") (class "Default")
      (node (ref "U6") (pin "27") (pinfunction "P4.2/WR_27") (pintype "input+no_connect"))
    )
    (net (code "85") (name "unconnected-(U6-P4.3{slash}SCLK_3-Pad28)") (class "Default")
      (node (ref "U6") (pin "28") (pinfunction "P4.3/SCLK_3_28") (pintype "input+no_connect"))
    )
    (net (code "86") (name "unconnected-(U6-P4.4{slash}RD-Pad29)") (class "Default")
      (node (ref "U6") (pin "29") (pinfunction "P4.4/RD_29") (pintype "input+no_connect"))
    )
    (net (code "87") (name "unconnected-(U6-P5.4{slash}RST{slash}MCLKO{slash}SS_3-Pad13)") (class "Default")
      (node (ref "U6") (pin "13") (pinfunction "P5.4/RST/MCLKO/SS_3_13") (pintype "input+no_connect"))
    )
    (net (code "88") (name "unconnected-(U6-P5.5-Pad15)") (class "Default")
      (node (ref "U6") (pin "15") (pinfunction "P5.5_15") (pintype "input+no_connect"))
    )
    (net (code "89") (name "unconnected-(U6-RXD2_2{slash}P4.6-Pad39)") (class "Default")
      (node (ref "U6") (pin "39") (pinfunction "RXD2_2/P4.6_39") (pintype "input+no_connect"))
    )
    (net (code "90") (name "unconnected-(U6-RXD2{slash}CCP1{slash}ADC0{slash}P1.0-Pad4)") (class "Default")
      (node (ref "U6") (pin "4") (pinfunction "RXD2/CCP1/ADC0/P1.0_4") (pintype "input+no_connect"))
    )
    (net (code "91") (name "unconnected-(U6-SCLK{slash}ADC5{slash}P1.5-Pad10)") (class "Default")
      (node (ref "U6") (pin "10") (pinfunction "SCLK/ADC5/P1.5_10") (pintype "input+no_connect"))
    )
    (net (code "92") (name "unconnected-(U6-TXD2_2{slash}P4.7-Pad6)") (class "Default")
      (node (ref "U6") (pin "6") (pinfunction "TXD2_2/P4.7_6") (pintype "input+no_connect"))
    )
    (net (code "93") (name "unconnected-(U6-TXD2{slash}CCP0{slash}ADC1{slash}P1.1-Pad5)") (class "Default")
      (node (ref "U6") (pin "5") (pinfunction "TXD2/CCP0/ADC1/P1.1_5") (pintype "input+no_connect"))
    )
    (net (code "94") (name "unconnected-(U6-XTAL1{slash}P1.7{slash}ADC7{slash}TXD_3-Pad12)") (class "Default")
      (node (ref "U6") (pin "12") (pinfunction "XTAL1/P1.7/ADC7/TXD_3_12") (pintype "input+no_connect"))
    )
    (net (code "95") (name "unconnected-(U6-XTAL2{slash}RXD_3{slash}ADC6{slash}P1.6-Pad11)") (class "Default")
      (node (ref "U6") (pin "11") (pinfunction "XTAL2/RXD_3/ADC6/P1.6_11") (pintype "input+no_connect"))
    )
    (net (code "96") (name "unconnected-(U7-QE-Pad4)") (class "Default")
      (node (ref "U7") (pin "4") (pinfunction "QE_4") (pintype "input+no_connect"))
    )
    (net (code "97") (name "unconnected-(U7-QF-Pad5)") (class "Default")
      (node (ref "U7") (pin "5") (pinfunction "QF_5") (pintype "input+no_connect"))
    )
    (net (code "98") (name "unconnected-(U7-QG-Pad6)") (class "Default")
      (node (ref "U7") (pin "6") (pinfunction "QG_6") (pintype "input+no_connect"))
    )
    (net (code "99") (name "unconnected-(U7-QH-Pad7)") (class "Default")
      (node (ref "U7") (pin "7") (pinfunction "QH_7") (pintype "input+no_connect"))
    )
    (net (code "100") (name "unconnected-(U7-SQH-Pad9)") (class "Default")
      (node (ref "U7") (pin "9") (pinfunction "SQH_9") (pintype "input+no_connect"))
    )
  )
)
